# LED.net
KiCad netlist of a schematic drawn in Altium Designer
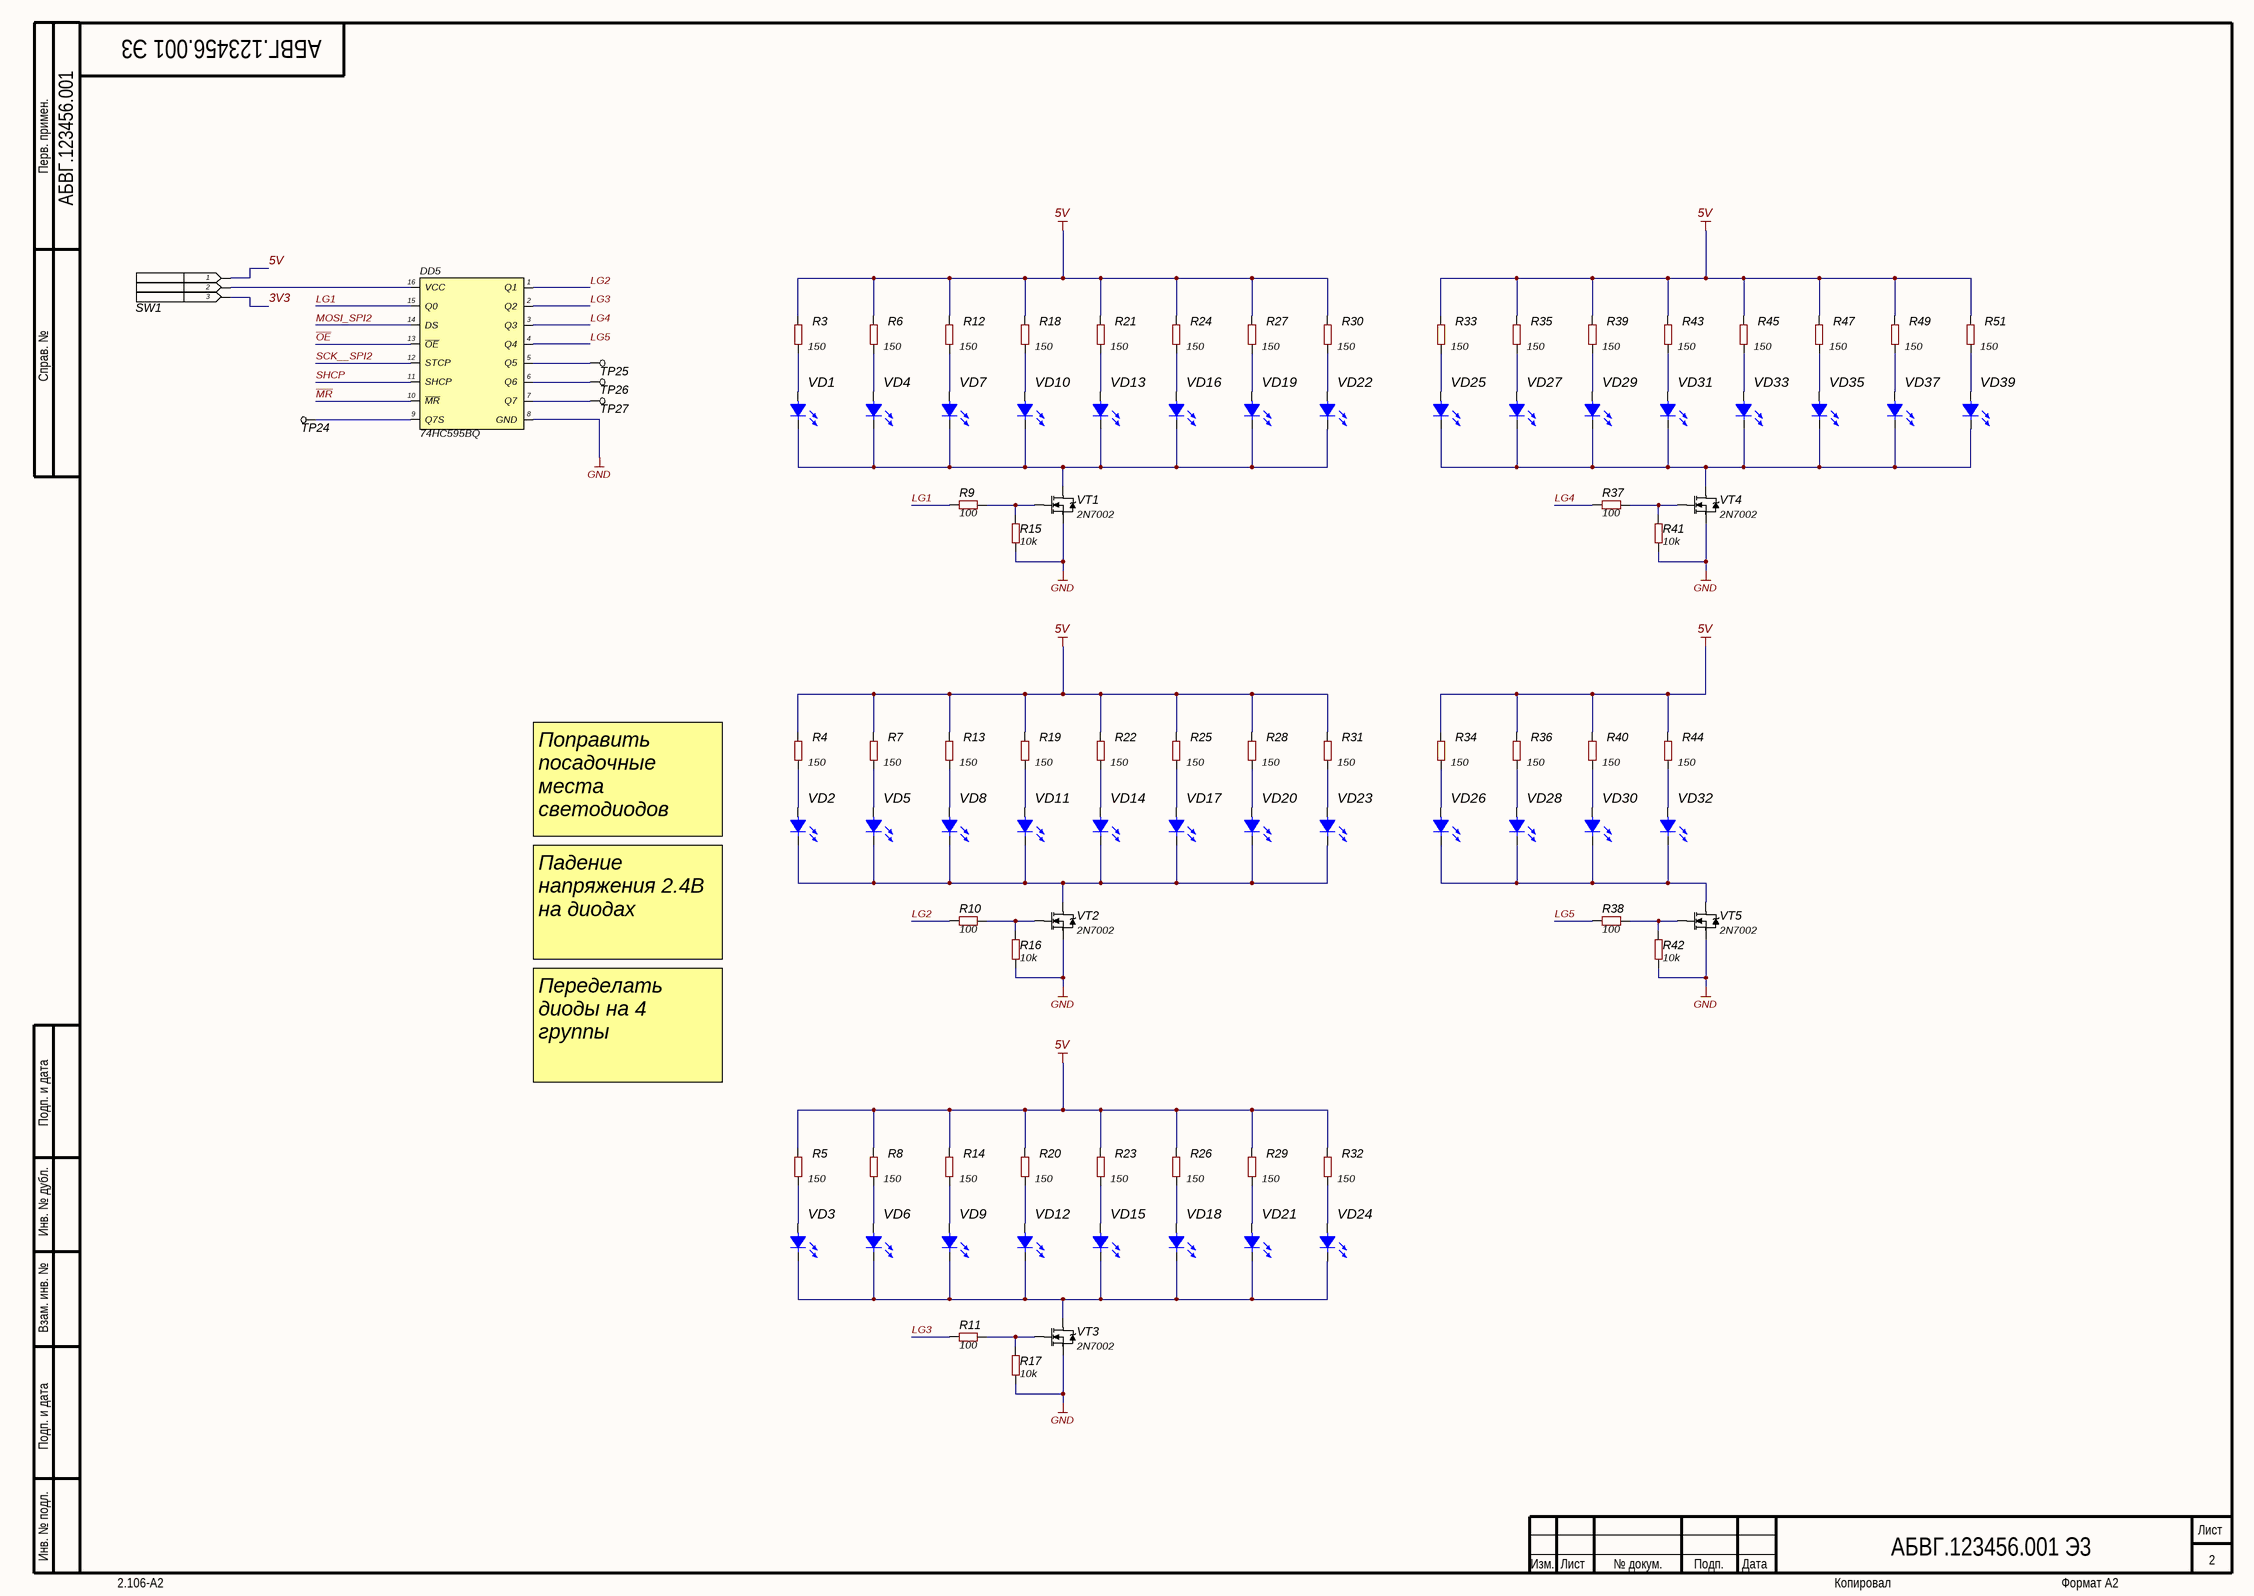
[diagram p0: LED.SchDoc]

(export (version "E")
  (design (tool "Eeschema 10.0.6"))
  (components
    (comp (ref "DD5")
      (value "74HC595BQ")
      (footprint "16-DHVQFN")
      (libsource (lib "ic-logic") (part "74HC595BQ"))
    )
    (comp (ref "R3")
      (value "150")
      (footprint "RES: 0603")
      (fields
        (field (name "MANUFACTURER") "Yageo")
        (field (name "PARTNUMBER") "RC0603JR-07100RL")
        (field (name "VALUEMANUFACTURERPARTNUMBER") "Resistor film, 150, , 0603, 0.1W, -55...+125°C")
      )
      (libsource (lib "resistor") (part "Resistor_0603"))
    )
    (comp (ref "R4")
      (value "150")
      (footprint "RES: 0603")
      (fields
        (field (name "MANUFACTURER") "Yageo")
        (field (name "PARTNUMBER") "RC0603JR-07100RL")
        (field (name "VALUEMANUFACTURERPARTNUMBER") "Resistor film, 150, , 0603, 0.1W, -55...+125°C")
      )
      (libsource (lib "resistor") (part "Resistor_0603"))
    )
    (comp (ref "R5")
      (value "150")
      (footprint "RES: 0603")
      (fields
        (field (name "MANUFACTURER") "Yageo")
        (field (name "PARTNUMBER") "RC0603JR-07100RL")
        (field (name "VALUEMANUFACTURERPARTNUMBER") "Resistor film, 150, , 0603, 0.1W, -55...+125°C")
      )
      (libsource (lib "resistor") (part "Resistor_0603"))
    )
    (comp (ref "R6")
      (value "150")
      (footprint "RES: 0603")
      (fields
        (field (name "MANUFACTURER") "Yageo")
        (field (name "PARTNUMBER") "RC0603JR-07100RL")
        (field (name "VALUEMANUFACTURERPARTNUMBER") "Resistor film, 150, , 0603, 0.1W, -55...+125°C")
      )
      (libsource (lib "resistor") (part "Resistor_0603"))
    )
    (comp (ref "R7")
      (value "150")
      (footprint "RES: 0603")
      (fields
        (field (name "MANUFACTURER") "Yageo")
        (field (name "PARTNUMBER") "RC0603JR-07100RL")
        (field (name "VALUEMANUFACTURERPARTNUMBER") "Resistor film, 150, , 0603, 0.1W, -55...+125°C")
      )
      (libsource (lib "resistor") (part "Resistor_0603"))
    )
    (comp (ref "R8")
      (value "150")
      (footprint "RES: 0603")
      (fields
        (field (name "MANUFACTURER") "Yageo")
        (field (name "PARTNUMBER") "RC0603JR-07100RL")
        (field (name "VALUEMANUFACTURERPARTNUMBER") "Resistor film, 150, , 0603, 0.1W, -55...+125°C")
      )
      (libsource (lib "resistor") (part "Resistor_0603"))
    )
    (comp (ref "R9")
      (value "100")
      (footprint "RES: 0603")
      (fields
        (field (name "MANUFACTURER") "Yageo")
        (field (name "PARTNUMBER") "RC0603JR-07100RL")
        (field (name "VALUEMANUFACTURERPARTNUMBER") "Resistor film, 100, , 0603, 0.1W, -55...+125°C")
      )
      (libsource (lib "") (part "Resistor_0603_1"))
    )
    (comp (ref "R10")
      (value "100")
      (footprint "RES: 0603")
      (fields
        (field (name "MANUFACTURER") "Yageo")
        (field (name "PARTNUMBER") "RC0603JR-07100RL")
        (field (name "VALUEMANUFACTURERPARTNUMBER") "Resistor film, 100, , 0603, 0.1W, -55...+125°C")
      )
      (libsource (lib "") (part "Resistor_0603_1"))
    )
    (comp (ref "R11")
      (value "100")
      (footprint "RES: 0603")
      (fields
        (field (name "MANUFACTURER") "Yageo")
        (field (name "PARTNUMBER") "RC0603JR-07100RL")
        (field (name "VALUEMANUFACTURERPARTNUMBER") "Resistor film, 100, , 0603, 0.1W, -55...+125°C")
      )
      (libsource (lib "") (part "Resistor_0603_1"))
    )
    (comp (ref "R12")
      (value "150")
      (footprint "RES: 0603")
      (fields
        (field (name "MANUFACTURER") "Yageo")
        (field (name "PARTNUMBER") "RC0603JR-07100RL")
        (field (name "VALUEMANUFACTURERPARTNUMBER") "Resistor film, 150, , 0603, 0.1W, -55...+125°C")
      )
      (libsource (lib "resistor") (part "Resistor_0603"))
    )
    (comp (ref "R13")
      (value "150")
      (footprint "RES: 0603")
      (fields
        (field (name "MANUFACTURER") "Yageo")
        (field (name "PARTNUMBER") "RC0603JR-07100RL")
        (field (name "VALUEMANUFACTURERPARTNUMBER") "Resistor film, 150, , 0603, 0.1W, -55...+125°C")
      )
      (libsource (lib "resistor") (part "Resistor_0603"))
    )
    (comp (ref "R14")
      (value "150")
      (footprint "RES: 0603")
      (fields
        (field (name "MANUFACTURER") "Yageo")
        (field (name "PARTNUMBER") "RC0603JR-07100RL")
        (field (name "VALUEMANUFACTURERPARTNUMBER") "Resistor film, 150, , 0603, 0.1W, -55...+125°C")
      )
      (libsource (lib "resistor") (part "Resistor_0603"))
    )
    (comp (ref "R15")
      (value "10k")
      (footprint "RES: 0603")
      (fields
        (field (name "MANUFACTURER") "Yageo")
        (field (name "PARTNUMBER") "RC0603JR-07100RL")
        (field (name "VALUEMANUFACTURERPARTNUMBER") "Resistor film, 10k, , 0603, 0.1W, -55...+125°C")
      )
      (libsource (lib "resistor") (part "Resistor_0603"))
    )
    (comp (ref "R16")
      (value "10k")
      (footprint "RES: 0603")
      (fields
        (field (name "MANUFACTURER") "Yageo")
        (field (name "PARTNUMBER") "RC0603JR-07100RL")
        (field (name "VALUEMANUFACTURERPARTNUMBER") "Resistor film, 10k, , 0603, 0.1W, -55...+125°C")
      )
      (libsource (lib "resistor") (part "Resistor_0603"))
    )
    (comp (ref "R17")
      (value "10k")
      (footprint "RES: 0603")
      (fields
        (field (name "MANUFACTURER") "Yageo")
        (field (name "PARTNUMBER") "RC0603JR-07100RL")
        (field (name "VALUEMANUFACTURERPARTNUMBER") "Resistor film, 10k, , 0603, 0.1W, -55...+125°C")
      )
      (libsource (lib "resistor") (part "Resistor_0603"))
    )
    (comp (ref "R18")
      (value "150")
      (footprint "RES: 0603")
      (fields
        (field (name "MANUFACTURER") "Yageo")
        (field (name "PARTNUMBER") "RC0603JR-07100RL")
        (field (name "VALUEMANUFACTURERPARTNUMBER") "Resistor film, 150, , 0603, 0.1W, -55...+125°C")
      )
      (libsource (lib "resistor") (part "Resistor_0603"))
    )
    (comp (ref "R19")
      (value "150")
      (footprint "RES: 0603")
      (fields
        (field (name "MANUFACTURER") "Yageo")
        (field (name "PARTNUMBER") "RC0603JR-07100RL")
        (field (name "VALUEMANUFACTURERPARTNUMBER") "Resistor film, 150, , 0603, 0.1W, -55...+125°C")
      )
      (libsource (lib "resistor") (part "Resistor_0603"))
    )
    (comp (ref "R20")
      (value "150")
      (footprint "RES: 0603")
      (fields
        (field (name "MANUFACTURER") "Yageo")
        (field (name "PARTNUMBER") "RC0603JR-07100RL")
        (field (name "VALUEMANUFACTURERPARTNUMBER") "Resistor film, 150, , 0603, 0.1W, -55...+125°C")
      )
      (libsource (lib "resistor") (part "Resistor_0603"))
    )
    (comp (ref "R21")
      (value "150")
      (footprint "RES: 0603")
      (fields
        (field (name "MANUFACTURER") "Yageo")
        (field (name "PARTNUMBER") "RC0603JR-07100RL")
        (field (name "VALUEMANUFACTURERPARTNUMBER") "Resistor film, 150, , 0603, 0.1W, -55...+125°C")
      )
      (libsource (lib "resistor") (part "Resistor_0603"))
    )
    (comp (ref "R22")
      (value "150")
      (footprint "RES: 0603")
      (fields
        (field (name "MANUFACTURER") "Yageo")
        (field (name "PARTNUMBER") "RC0603JR-07100RL")
        (field (name "VALUEMANUFACTURERPARTNUMBER") "Resistor film, 150, , 0603, 0.1W, -55...+125°C")
      )
      (libsource (lib "resistor") (part "Resistor_0603"))
    )
    (comp (ref "R23")
      (value "150")
      (footprint "RES: 0603")
      (fields
        (field (name "MANUFACTURER") "Yageo")
        (field (name "PARTNUMBER") "RC0603JR-07100RL")
        (field (name "VALUEMANUFACTURERPARTNUMBER") "Resistor film, 150, , 0603, 0.1W, -55...+125°C")
      )
      (libsource (lib "resistor") (part "Resistor_0603"))
    )
    (comp (ref "R24")
      (value "150")
      (footprint "RES: 0603")
      (fields
        (field (name "MANUFACTURER") "Yageo")
        (field (name "PARTNUMBER") "RC0603JR-07100RL")
        (field (name "VALUEMANUFACTURERPARTNUMBER") "Resistor film, 150, , 0603, 0.1W, -55...+125°C")
      )
      (libsource (lib "resistor") (part "Resistor_0603"))
    )
    (comp (ref "R25")
      (value "150")
      (footprint "RES: 0603")
      (fields
        (field (name "MANUFACTURER") "Yageo")
        (field (name "PARTNUMBER") "RC0603JR-07100RL")
        (field (name "VALUEMANUFACTURERPARTNUMBER") "Resistor film, 150, , 0603, 0.1W, -55...+125°C")
      )
      (libsource (lib "resistor") (part "Resistor_0603"))
    )
    (comp (ref "R26")
      (value "150")
      (footprint "RES: 0603")
      (fields
        (field (name "MANUFACTURER") "Yageo")
        (field (name "PARTNUMBER") "RC0603JR-07100RL")
        (field (name "VALUEMANUFACTURERPARTNUMBER") "Resistor film, 150, , 0603, 0.1W, -55...+125°C")
      )
      (libsource (lib "resistor") (part "Resistor_0603"))
    )
    (comp (ref "R27")
      (value "150")
      (footprint "RES: 0603")
      (fields
        (field (name "MANUFACTURER") "Yageo")
        (field (name "PARTNUMBER") "RC0603JR-07100RL")
        (field (name "VALUEMANUFACTURERPARTNUMBER") "Resistor film, 150, , 0603, 0.1W, -55...+125°C")
      )
      (libsource (lib "resistor") (part "Resistor_0603"))
    )
    (comp (ref "R28")
      (value "150")
      (footprint "RES: 0603")
      (fields
        (field (name "MANUFACTURER") "Yageo")
        (field (name "PARTNUMBER") "RC0603JR-07100RL")
        (field (name "VALUEMANUFACTURERPARTNUMBER") "Resistor film, 150, , 0603, 0.1W, -55...+125°C")
      )
      (libsource (lib "resistor") (part "Resistor_0603"))
    )
    (comp (ref "R29")
      (value "150")
      (footprint "RES: 0603")
      (fields
        (field (name "MANUFACTURER") "Yageo")
        (field (name "PARTNUMBER") "RC0603JR-07100RL")
        (field (name "VALUEMANUFACTURERPARTNUMBER") "Resistor film, 150, , 0603, 0.1W, -55...+125°C")
      )
      (libsource (lib "resistor") (part "Resistor_0603"))
    )
    (comp (ref "R30")
      (value "150")
      (footprint "RES: 0603")
      (fields
        (field (name "MANUFACTURER") "Yageo")
        (field (name "PARTNUMBER") "RC0603JR-07100RL")
        (field (name "VALUEMANUFACTURERPARTNUMBER") "Resistor film, 150, , 0603, 0.1W, -55...+125°C")
      )
      (libsource (lib "resistor") (part "Resistor_0603"))
    )
    (comp (ref "R31")
      (value "150")
      (footprint "RES: 0603")
      (fields
        (field (name "MANUFACTURER") "Yageo")
        (field (name "PARTNUMBER") "RC0603JR-07100RL")
        (field (name "VALUEMANUFACTURERPARTNUMBER") "Resistor film, 150, , 0603, 0.1W, -55...+125°C")
      )
      (libsource (lib "resistor") (part "Resistor_0603"))
    )
    (comp (ref "R32")
      (value "150")
      (footprint "RES: 0603")
      (fields
        (field (name "MANUFACTURER") "Yageo")
        (field (name "PARTNUMBER") "RC0603JR-07100RL")
        (field (name "VALUEMANUFACTURERPARTNUMBER") "Resistor film, 150, , 0603, 0.1W, -55...+125°C")
      )
      (libsource (lib "resistor") (part "Resistor_0603"))
    )
    (comp (ref "R33")
      (value "150")
      (footprint "RES: 0603")
      (fields
        (field (name "MANUFACTURER") "Yageo")
        (field (name "PARTNUMBER") "RC0603JR-07100RL")
        (field (name "VALUEMANUFACTURERPARTNUMBER") "Resistor film, 150, , 0603, 0.1W, -55...+125°C")
      )
      (libsource (lib "resistor") (part "Resistor_0603"))
    )
    (comp (ref "R34")
      (value "150")
      (footprint "RES: 0603")
      (fields
        (field (name "MANUFACTURER") "Yageo")
        (field (name "PARTNUMBER") "RC0603JR-07100RL")
        (field (name "VALUEMANUFACTURERPARTNUMBER") "Resistor film, 150, , 0603, 0.1W, -55...+125°C")
      )
      (libsource (lib "resistor") (part "Resistor_0603"))
    )
    (comp (ref "R35")
      (value "150")
      (footprint "RES: 0603")
      (fields
        (field (name "MANUFACTURER") "Yageo")
        (field (name "PARTNUMBER") "RC0603JR-07100RL")
        (field (name "VALUEMANUFACTURERPARTNUMBER") "Resistor film, 150, , 0603, 0.1W, -55...+125°C")
      )
      (libsource (lib "resistor") (part "Resistor_0603"))
    )
    (comp (ref "R36")
      (value "150")
      (footprint "RES: 0603")
      (fields
        (field (name "MANUFACTURER") "Yageo")
        (field (name "PARTNUMBER") "RC0603JR-07100RL")
        (field (name "VALUEMANUFACTURERPARTNUMBER") "Resistor film, 150, , 0603, 0.1W, -55...+125°C")
      )
      (libsource (lib "resistor") (part "Resistor_0603"))
    )
    (comp (ref "R37")
      (value "100")
      (footprint "RES: 0603")
      (fields
        (field (name "MANUFACTURER") "Yageo")
        (field (name "PARTNUMBER") "RC0603JR-07100RL")
        (field (name "VALUEMANUFACTURERPARTNUMBER") "Resistor film, 100, , 0603, 0.1W, -55...+125°C")
      )
      (libsource (lib "") (part "Resistor_0603_1"))
    )
    (comp (ref "R38")
      (value "100")
      (footprint "RES: 0603")
      (fields
        (field (name "MANUFACTURER") "Yageo")
        (field (name "PARTNUMBER") "RC0603JR-07100RL")
        (field (name "VALUEMANUFACTURERPARTNUMBER") "Resistor film, 100, , 0603, 0.1W, -55...+125°C")
      )
      (libsource (lib "") (part "Resistor_0603_1"))
    )
    (comp (ref "R39")
      (value "150")
      (footprint "RES: 0603")
      (fields
        (field (name "MANUFACTURER") "Yageo")
        (field (name "PARTNUMBER") "RC0603JR-07100RL")
        (field (name "VALUEMANUFACTURERPARTNUMBER") "Resistor film, 150, , 0603, 0.1W, -55...+125°C")
      )
      (libsource (lib "resistor") (part "Resistor_0603"))
    )
    (comp (ref "R40")
      (value "150")
      (footprint "RES: 0603")
      (fields
        (field (name "MANUFACTURER") "Yageo")
        (field (name "PARTNUMBER") "RC0603JR-07100RL")
        (field (name "VALUEMANUFACTURERPARTNUMBER") "Resistor film, 150, , 0603, 0.1W, -55...+125°C")
      )
      (libsource (lib "resistor") (part "Resistor_0603"))
    )
    (comp (ref "R41")
      (value "10k")
      (footprint "RES: 0603")
      (fields
        (field (name "MANUFACTURER") "Yageo")
        (field (name "PARTNUMBER") "RC0603JR-07100RL")
        (field (name "VALUEMANUFACTURERPARTNUMBER") "Resistor film, 10k, , 0603, 0.1W, -55...+125°C")
      )
      (libsource (lib "resistor") (part "Resistor_0603"))
    )
    (comp (ref "R42")
      (value "10k")
      (footprint "RES: 0603")
      (fields
        (field (name "MANUFACTURER") "Yageo")
        (field (name "PARTNUMBER") "RC0603JR-07100RL")
        (field (name "VALUEMANUFACTURERPARTNUMBER") "Resistor film, 10k, , 0603, 0.1W, -55...+125°C")
      )
      (libsource (lib "resistor") (part "Resistor_0603"))
    )
    (comp (ref "R43")
      (value "150")
      (footprint "RES: 0603")
      (fields
        (field (name "MANUFACTURER") "Yageo")
        (field (name "PARTNUMBER") "RC0603JR-07100RL")
        (field (name "VALUEMANUFACTURERPARTNUMBER") "Resistor film, 150, , 0603, 0.1W, -55...+125°C")
      )
      (libsource (lib "resistor") (part "Resistor_0603"))
    )
    (comp (ref "R44")
      (value "150")
      (footprint "RES: 0603")
      (fields
        (field (name "MANUFACTURER") "Yageo")
        (field (name "PARTNUMBER") "RC0603JR-07100RL")
        (field (name "VALUEMANUFACTURERPARTNUMBER") "Resistor film, 150, , 0603, 0.1W, -55...+125°C")
      )
      (libsource (lib "resistor") (part "Resistor_0603"))
    )
    (comp (ref "R45")
      (value "150")
      (footprint "RES: 0603")
      (fields
        (field (name "MANUFACTURER") "Yageo")
        (field (name "PARTNUMBER") "RC0603JR-07100RL")
        (field (name "VALUEMANUFACTURERPARTNUMBER") "Resistor film, 150, , 0603, 0.1W, -55...+125°C")
      )
      (libsource (lib "resistor") (part "Resistor_0603"))
    )
    (comp (ref "R47")
      (value "150")
      (footprint "RES: 0603")
      (fields
        (field (name "MANUFACTURER") "Yageo")
        (field (name "PARTNUMBER") "RC0603JR-07100RL")
        (field (name "VALUEMANUFACTURERPARTNUMBER") "Resistor film, 150, , 0603, 0.1W, -55...+125°C")
      )
      (libsource (lib "resistor") (part "Resistor_0603"))
    )
    (comp (ref "R49")
      (value "150")
      (footprint "RES: 0603")
      (fields
        (field (name "MANUFACTURER") "Yageo")
        (field (name "PARTNUMBER") "RC0603JR-07100RL")
        (field (name "VALUEMANUFACTURERPARTNUMBER") "Resistor film, 150, , 0603, 0.1W, -55...+125°C")
      )
      (libsource (lib "resistor") (part "Resistor_0603"))
    )
    (comp (ref "R51")
      (value "150")
      (footprint "RES: 0603")
      (fields
        (field (name "MANUFACTURER") "Yageo")
        (field (name "PARTNUMBER") "RC0603JR-07100RL")
        (field (name "VALUEMANUFACTURERPARTNUMBER") "Resistor film, 150, , 0603, 0.1W, -55...+125°C")
      )
      (libsource (lib "resistor") (part "Resistor_0603"))
    )
    (comp (ref "SW1")
      (value "Jumper")
      (footprint "JUM: 0603_3P")
      (description "N/C")
      (libsource (lib "electromechanics") (part "Jumper"))
    )
    (comp (ref "TP24")
      (value "Testpoint_HS1mm")
      (footprint "TestPoint(without hole)")
      (libsource (lib "connector") (part "Testpoint_HS1mm"))
    )
    (comp (ref "TP25")
      (value "Testpoint_HS1mm")
      (footprint "TestPoint(without hole)")
      (libsource (lib "connector") (part "Testpoint_HS1mm"))
    )
    (comp (ref "TP26")
      (value "Testpoint_HS1mm")
      (footprint "TestPoint(without hole)")
      (libsource (lib "connector") (part "Testpoint_HS1mm"))
    )
    (comp (ref "TP27")
      (value "Testpoint_HS1mm")
      (footprint "TestPoint(without hole)")
      (libsource (lib "connector") (part "Testpoint_HS1mm"))
    )
    (comp (ref "VD1")
      (value "~")
      (footprint "LED: 1206Y")
      (fields (field (name "VALUEMANUFACTURERPARTNUMBER") "LED, Green, *, *, *, -55...+150°C"))
      (libsource (lib "diode") (part "LED_single"))
    )
    (comp (ref "VD2")
      (value "~")
      (footprint "LED: 1206Y")
      (fields (field (name "VALUEMANUFACTURERPARTNUMBER") "LED, Green, *, *, *, -55...+150°C"))
      (libsource (lib "diode") (part "LED_single"))
    )
    (comp (ref "VD3")
      (value "~")
      (footprint "LED: 1206Y")
      (fields (field (name "VALUEMANUFACTURERPARTNUMBER") "LED, Green, *, *, *, -55...+150°C"))
      (libsource (lib "diode") (part "LED_single"))
    )
    (comp (ref "VD4")
      (value "~")
      (footprint "LED: 1206Y")
      (fields (field (name "VALUEMANUFACTURERPARTNUMBER") "LED, Green, *, *, *, -55...+150°C"))
      (libsource (lib "diode") (part "LED_single"))
    )
    (comp (ref "VD5")
      (value "~")
      (footprint "LED: 1206Y")
      (fields (field (name "VALUEMANUFACTURERPARTNUMBER") "LED, Green, *, *, *, -55...+150°C"))
      (libsource (lib "diode") (part "LED_single"))
    )
    (comp (ref "VD6")
      (value "~")
      (footprint "LED: 1206Y")
      (fields (field (name "VALUEMANUFACTURERPARTNUMBER") "LED, Green, *, *, *, -55...+150°C"))
      (libsource (lib "diode") (part "LED_single"))
    )
    (comp (ref "VD7")
      (value "~")
      (footprint "LED: 1206Y")
      (fields (field (name "VALUEMANUFACTURERPARTNUMBER") "LED, Green, *, *, *, -55...+150°C"))
      (libsource (lib "diode") (part "LED_single"))
    )
    (comp (ref "VD8")
      (value "~")
      (footprint "LED: 1206Y")
      (fields (field (name "VALUEMANUFACTURERPARTNUMBER") "LED, Green, *, *, *, -55...+150°C"))
      (libsource (lib "diode") (part "LED_single"))
    )
    (comp (ref "VD9")
      (value "~")
      (footprint "LED: 1206Y")
      (fields (field (name "VALUEMANUFACTURERPARTNUMBER") "LED, Green, *, *, *, -55...+150°C"))
      (libsource (lib "diode") (part "LED_single"))
    )
    (comp (ref "VD10")
      (value "~")
      (footprint "LED: 1206Y")
      (fields (field (name "VALUEMANUFACTURERPARTNUMBER") "LED, Green, *, *, *, -55...+150°C"))
      (libsource (lib "diode") (part "LED_single"))
    )
    (comp (ref "VD11")
      (value "~")
      (footprint "LED: 1206Y")
      (fields (field (name "VALUEMANUFACTURERPARTNUMBER") "LED, Green, *, *, *, -55...+150°C"))
      (libsource (lib "diode") (part "LED_single"))
    )
    (comp (ref "VD12")
      (value "~")
      (footprint "LED: 1206Y")
      (fields (field (name "VALUEMANUFACTURERPARTNUMBER") "LED, Green, *, *, *, -55...+150°C"))
      (libsource (lib "diode") (part "LED_single"))
    )
    (comp (ref "VD13")
      (value "~")
      (footprint "LED: 1206Y")
      (fields (field (name "VALUEMANUFACTURERPARTNUMBER") "LED, Green, *, *, *, -55...+150°C"))
      (libsource (lib "diode") (part "LED_single"))
    )
    (comp (ref "VD14")
      (value "~")
      (footprint "LED: 1206Y")
      (fields (field (name "VALUEMANUFACTURERPARTNUMBER") "LED, Green, *, *, *, -55...+150°C"))
      (libsource (lib "diode") (part "LED_single"))
    )
    (comp (ref "VD15")
      (value "~")
      (footprint "LED: 1206Y")
      (fields (field (name "VALUEMANUFACTURERPARTNUMBER") "LED, Green, *, *, *, -55...+150°C"))
      (libsource (lib "diode") (part "LED_single"))
    )
    (comp (ref "VD16")
      (value "~")
      (footprint "LED: 1206Y")
      (fields (field (name "VALUEMANUFACTURERPARTNUMBER") "LED, Green, *, *, *, -55...+150°C"))
      (libsource (lib "diode") (part "LED_single"))
    )
    (comp (ref "VD17")
      (value "~")
      (footprint "LED: 1206Y")
      (fields (field (name "VALUEMANUFACTURERPARTNUMBER") "LED, Green, *, *, *, -55...+150°C"))
      (libsource (lib "diode") (part "LED_single"))
    )
    (comp (ref "VD18")
      (value "~")
      (footprint "LED: 1206Y")
      (fields (field (name "VALUEMANUFACTURERPARTNUMBER") "LED, Green, *, *, *, -55...+150°C"))
      (libsource (lib "diode") (part "LED_single"))
    )
    (comp (ref "VD19")
      (value "~")
      (footprint "LED: 1206Y")
      (fields (field (name "VALUEMANUFACTURERPARTNUMBER") "LED, Green, *, *, *, -55...+150°C"))
      (libsource (lib "diode") (part "LED_single"))
    )
    (comp (ref "VD20")
      (value "~")
      (footprint "LED: 1206Y")
      (fields (field (name "VALUEMANUFACTURERPARTNUMBER") "LED, Green, *, *, *, -55...+150°C"))
      (libsource (lib "diode") (part "LED_single"))
    )
    (comp (ref "VD21")
      (value "~")
      (footprint "LED: 1206Y")
      (fields (field (name "VALUEMANUFACTURERPARTNUMBER") "LED, Green, *, *, *, -55...+150°C"))
      (libsource (lib "diode") (part "LED_single"))
    )
    (comp (ref "VD22")
      (value "~")
      (footprint "LED: 1206Y")
      (fields (field (name "VALUEMANUFACTURERPARTNUMBER") "LED, Green, *, *, *, -55...+150°C"))
      (libsource (lib "diode") (part "LED_single"))
    )
    (comp (ref "VD23")
      (value "~")
      (footprint "LED: 1206Y")
      (fields (field (name "VALUEMANUFACTURERPARTNUMBER") "LED, Green, *, *, *, -55...+150°C"))
      (libsource (lib "diode") (part "LED_single"))
    )
    (comp (ref "VD24")
      (value "~")
      (footprint "LED: 1206Y")
      (fields (field (name "VALUEMANUFACTURERPARTNUMBER") "LED, Green, *, *, *, -55...+150°C"))
      (libsource (lib "diode") (part "LED_single"))
    )
    (comp (ref "VD25")
      (value "~")
      (footprint "LED: 1206Y")
      (fields (field (name "VALUEMANUFACTURERPARTNUMBER") "LED, Green, *, *, *, -55...+150°C"))
      (libsource (lib "diode") (part "LED_single"))
    )
    (comp (ref "VD26")
      (value "~")
      (footprint "LED: 1206Y")
      (fields (field (name "VALUEMANUFACTURERPARTNUMBER") "LED, Green, *, *, *, -55...+150°C"))
      (libsource (lib "diode") (part "LED_single"))
    )
    (comp (ref "VD27")
      (value "~")
      (footprint "LED: 1206Y")
      (fields (field (name "VALUEMANUFACTURERPARTNUMBER") "LED, Green, *, *, *, -55...+150°C"))
      (libsource (lib "diode") (part "LED_single"))
    )
    (comp (ref "VD28")
      (value "~")
      (footprint "LED: 1206Y")
      (fields (field (name "VALUEMANUFACTURERPARTNUMBER") "LED, Green, *, *, *, -55...+150°C"))
      (libsource (lib "diode") (part "LED_single"))
    )
    (comp (ref "VD29")
      (value "~")
      (footprint "LED: 1206Y")
      (fields (field (name "VALUEMANUFACTURERPARTNUMBER") "LED, Green, *, *, *, -55...+150°C"))
      (libsource (lib "diode") (part "LED_single"))
    )
    (comp (ref "VD30")
      (value "~")
      (footprint "LED: 1206Y")
      (fields (field (name "VALUEMANUFACTURERPARTNUMBER") "LED, Green, *, *, *, -55...+150°C"))
      (libsource (lib "diode") (part "LED_single"))
    )
    (comp (ref "VD31")
      (value "~")
      (footprint "LED: 1206Y")
      (fields (field (name "VALUEMANUFACTURERPARTNUMBER") "LED, Green, *, *, *, -55...+150°C"))
      (libsource (lib "diode") (part "LED_single"))
    )
    (comp (ref "VD32")
      (value "~")
      (footprint "LED: 1206Y")
      (fields (field (name "VALUEMANUFACTURERPARTNUMBER") "LED, Green, *, *, *, -55...+150°C"))
      (libsource (lib "diode") (part "LED_single"))
    )
    (comp (ref "VD33")
      (value "~")
      (footprint "LED: 1206Y")
      (fields (field (name "VALUEMANUFACTURERPARTNUMBER") "LED, Green, *, *, *, -55...+150°C"))
      (libsource (lib "diode") (part "LED_single"))
    )
    (comp (ref "VD35")
      (value "~")
      (footprint "LED: 1206Y")
      (fields (field (name "VALUEMANUFACTURERPARTNUMBER") "LED, Green, *, *, *, -55...+150°C"))
      (libsource (lib "diode") (part "LED_single"))
    )
    (comp (ref "VD37")
      (value "~")
      (footprint "LED: 1206Y")
      (fields (field (name "VALUEMANUFACTURERPARTNUMBER") "LED, Green, *, *, *, -55...+150°C"))
      (libsource (lib "diode") (part "LED_single"))
    )
    (comp (ref "VD39")
      (value "~")
      (footprint "LED: 1206Y")
      (fields (field (name "VALUEMANUFACTURERPARTNUMBER") "LED, Green, *, *, *, -55...+150°C"))
      (libsource (lib "diode") (part "LED_single"))
    )
    (comp (ref "VT1")
      (value "~")
      (footprint "SOT23")
      (fields
        (field (name "MANUFACTURER") "Infineon Technologies")
        (field (name "VALUEMANUFACTURERPARTNUMBER") "MOSFET N-channel transistor, 80V, 7A, 9.1nC, 2.5W, 34mOhm, 756pF, 8-TDSON, -55...+150°C")
        (field (name "PARTNUMBER") "2N7002")
      )
      (libsource (lib "transistor") (part "MOSFET_N_132"))
    )
    (comp (ref "VT2")
      (value "~")
      (footprint "SOT23")
      (fields
        (field (name "MANUFACTURER") "Infineon Technologies")
        (field (name "VALUEMANUFACTURERPARTNUMBER") "MOSFET N-channel transistor, 80V, 7A, 9.1nC, 2.5W, 34mOhm, 756pF, 8-TDSON, -55...+150°C")
        (field (name "PARTNUMBER") "2N7002")
      )
      (libsource (lib "transistor") (part "MOSFET_N_132"))
    )
    (comp (ref "VT3")
      (value "~")
      (footprint "SOT23")
      (fields
        (field (name "MANUFACTURER") "Infineon Technologies")
        (field (name "VALUEMANUFACTURERPARTNUMBER") "MOSFET N-channel transistor, 80V, 7A, 9.1nC, 2.5W, 34mOhm, 756pF, 8-TDSON, -55...+150°C")
        (field (name "PARTNUMBER") "2N7002")
      )
      (libsource (lib "transistor") (part "MOSFET_N_132"))
    )
    (comp (ref "VT4")
      (value "~")
      (footprint "SOT23")
      (fields
        (field (name "MANUFACTURER") "Infineon Technologies")
        (field (name "VALUEMANUFACTURERPARTNUMBER") "MOSFET N-channel transistor, 80V, 7A, 9.1nC, 2.5W, 34mOhm, 756pF, 8-TDSON, -55...+150°C")
        (field (name "PARTNUMBER") "2N7002")
      )
      (libsource (lib "transistor") (part "MOSFET_N_132"))
    )
    (comp (ref "VT5")
      (value "~")
      (footprint "SOT23")
      (fields
        (field (name "MANUFACTURER") "Infineon Technologies")
        (field (name "VALUEMANUFACTURERPARTNUMBER") "MOSFET N-channel transistor, 80V, 7A, 9.1nC, 2.5W, 34mOhm, 756pF, 8-TDSON, -55...+150°C")
        (field (name "PARTNUMBER") "2N7002")
      )
      (libsource (lib "transistor") (part "MOSFET_N_132"))
    )
  )
  (nets
    (net (code "1") (name "/3V3") (class "Default")
      (node (ref "SW1") (pin "3") (pinfunction "3_3") (pintype "passive"))
    )
    (net (code "2") (name "/LG1") (class "Default")
      (node (ref "DD5") (pin "15") (pinfunction "Q0_15") (pintype "passive"))
      (node (ref "R9") (pin "1") (pinfunction "1_1") (pintype "passive"))
    )
    (net (code "3") (name "/LG2") (class "Default")
      (node (ref "DD5") (pin "1") (pinfunction "Q1_1") (pintype "passive"))
      (node (ref "R10") (pin "1") (pinfunction "1_1") (pintype "passive"))
    )
    (net (code "4") (name "/LG3") (class "Default")
      (node (ref "DD5") (pin "2") (pinfunction "Q2_2") (pintype "passive"))
      (node (ref "R11") (pin "1") (pinfunction "1_1") (pintype "passive"))
    )
    (net (code "5") (name "/LG4") (class "Default")
      (node (ref "DD5") (pin "3") (pinfunction "Q3_3") (pintype "passive"))
      (node (ref "R37") (pin "1") (pinfunction "1_1") (pintype "passive"))
    )
    (net (code "6") (name "/LG5") (class "Default")
      (node (ref "DD5") (pin "4") (pinfunction "Q4_4") (pintype "passive"))
      (node (ref "R38") (pin "1") (pinfunction "1_1") (pintype "passive"))
    )
    (net (code "7") (name "/MOSI_SPI2") (class "Default")
      (node (ref "DD5") (pin "14") (pinfunction "DS_14") (pintype "passive"))
    )
    (net (code "8") (name "/SCK__SPI2") (class "Default")
      (node (ref "DD5") (pin "12") (pinfunction "STCP_12") (pintype "passive"))
    )
    (net (code "9") (name "/SHCP") (class "Default")
      (node (ref "DD5") (pin "11") (pinfunction "SHCP_11") (pintype "passive"))
    )
    (net (code "10") (name "/~{MR}") (class "Default")
      (node (ref "DD5") (pin "10") (pinfunction "~{MR}_10") (pintype "passive"))
    )
    (net (code "11") (name "/~{OE}") (class "Default")
      (node (ref "DD5") (pin "13") (pinfunction "~{OE}_13") (pintype "passive"))
    )
    (net (code "12") (name "5V") (class "Default")
      (node (ref "R12") (pin "2") (pinfunction "2_2") (pintype "passive"))
      (node (ref "R13") (pin "2") (pinfunction "2_2") (pintype "passive"))
      (node (ref "R14") (pin "2") (pinfunction "2_2") (pintype "passive"))
      (node (ref "R18") (pin "2") (pinfunction "2_2") (pintype "passive"))
      (node (ref "R19") (pin "2") (pinfunction "2_2") (pintype "passive"))
      (node (ref "R20") (pin "2") (pinfunction "2_2") (pintype "passive"))
      (node (ref "R21") (pin "2") (pinfunction "2_2") (pintype "passive"))
      (node (ref "R22") (pin "2") (pinfunction "2_2") (pintype "passive"))
      (node (ref "R23") (pin "2") (pinfunction "2_2") (pintype "passive"))
      (node (ref "R24") (pin "2") (pinfunction "2_2") (pintype "passive"))
      (node (ref "R25") (pin "2") (pinfunction "2_2") (pintype "passive"))
      (node (ref "R26") (pin "2") (pinfunction "2_2") (pintype "passive"))
      (node (ref "R27") (pin "2") (pinfunction "2_2") (pintype "passive"))
      (node (ref "R28") (pin "2") (pinfunction "2_2") (pintype "passive"))
      (node (ref "R29") (pin "2") (pinfunction "2_2") (pintype "passive"))
      (node (ref "R3") (pin "2") (pinfunction "2_2") (pintype "passive"))
      (node (ref "R30") (pin "2") (pinfunction "2_2") (pintype "passive"))
      (node (ref "R31") (pin "2") (pinfunction "2_2") (pintype "passive"))
      (node (ref "R32") (pin "2") (pinfunction "2_2") (pintype "passive"))
      (node (ref "R33") (pin "2") (pinfunction "2_2") (pintype "passive"))
      (node (ref "R34") (pin "2") (pinfunction "2_2") (pintype "passive"))
      (node (ref "R35") (pin "2") (pinfunction "2_2") (pintype "passive"))
      (node (ref "R36") (pin "2") (pinfunction "2_2") (pintype "passive"))
      (node (ref "R39") (pin "2") (pinfunction "2_2") (pintype "passive"))
      (node (ref "R4") (pin "2") (pinfunction "2_2") (pintype "passive"))
      (node (ref "R40") (pin "2") (pinfunction "2_2") (pintype "passive"))
      (node (ref "R43") (pin "2") (pinfunction "2_2") (pintype "passive"))
      (node (ref "R44") (pin "2") (pinfunction "2_2") (pintype "passive"))
      (node (ref "R45") (pin "2") (pinfunction "2_2") (pintype "passive"))
      (node (ref "R47") (pin "2") (pinfunction "2_2") (pintype "passive"))
      (node (ref "R49") (pin "2") (pinfunction "2_2") (pintype "passive"))
      (node (ref "R5") (pin "2") (pinfunction "2_2") (pintype "passive"))
      (node (ref "R51") (pin "2") (pinfunction "2_2") (pintype "passive"))
      (node (ref "R6") (pin "2") (pinfunction "2_2") (pintype "passive"))
      (node (ref "R7") (pin "2") (pinfunction "2_2") (pintype "passive"))
      (node (ref "R8") (pin "2") (pinfunction "2_2") (pintype "passive"))
      (node (ref "SW1") (pin "1") (pinfunction "1_1") (pintype "passive"))
    )
    (net (code "13") (name "GND") (class "Default")
      (node (ref "DD5") (pin "8") (pinfunction "GND_8") (pintype "passive"))
      (node (ref "R15") (pin "1") (pinfunction "1_1") (pintype "passive"))
      (node (ref "R16") (pin "1") (pinfunction "1_1") (pintype "passive"))
      (node (ref "R17") (pin "1") (pinfunction "1_1") (pintype "passive"))
      (node (ref "R41") (pin "1") (pinfunction "1_1") (pintype "passive"))
      (node (ref "R42") (pin "1") (pinfunction "1_1") (pintype "passive"))
      (node (ref "VT1") (pin "2") (pinfunction "S_2") (pintype "passive"))
      (node (ref "VT2") (pin "2") (pinfunction "S_2") (pintype "passive"))
      (node (ref "VT3") (pin "2") (pinfunction "S_2") (pintype "passive"))
      (node (ref "VT4") (pin "2") (pinfunction "S_2") (pintype "passive"))
      (node (ref "VT5") (pin "2") (pinfunction "S_2") (pintype "passive"))
    )
    (net (code "14") (name "Net-(DD5-Q5)") (class "Default")
      (node (ref "DD5") (pin "5") (pinfunction "Q5_5") (pintype "passive"))
      (node (ref "TP25") (pin "1") (pinfunction "1_1") (pintype "passive"))
    )
    (net (code "15") (name "Net-(DD5-Q6)") (class "Default")
      (node (ref "DD5") (pin "6") (pinfunction "Q6_6") (pintype "passive"))
      (node (ref "TP26") (pin "1") (pinfunction "1_1") (pintype "passive"))
    )
    (net (code "16") (name "Net-(DD5-Q7)") (class "Default")
      (node (ref "DD5") (pin "7") (pinfunction "Q7_7") (pintype "passive"))
      (node (ref "TP27") (pin "1") (pinfunction "1_1") (pintype "passive"))
    )
    (net (code "17") (name "Net-(DD5-Q7S)") (class "Default")
      (node (ref "DD5") (pin "9") (pinfunction "Q7S_9") (pintype "passive"))
      (node (ref "TP24") (pin "1") (pinfunction "1_1") (pintype "passive"))
    )
    (net (code "18") (name "Net-(DD5-VCC)") (class "Default")
      (node (ref "DD5") (pin "16") (pinfunction "VCC_16") (pintype "passive"))
      (node (ref "SW1") (pin "2") (pinfunction "2_2") (pintype "passive"))
    )
    (net (code "19") (name "Net-(VD1-A)") (class "Default")
      (node (ref "R3") (pin "1") (pinfunction "1_1") (pintype "passive"))
      (node (ref "VD1") (pin "1") (pinfunction "A_1") (pintype "passive"))
    )
    (net (code "20") (name "Net-(VD1-C)") (class "Default")
      (node (ref "VD1") (pin "2") (pinfunction "C_2") (pintype "passive"))
      (node (ref "VD10") (pin "2") (pinfunction "C_2") (pintype "passive"))
      (node (ref "VD13") (pin "2") (pinfunction "C_2") (pintype "passive"))
      (node (ref "VD16") (pin "2") (pinfunction "C_2") (pintype "passive"))
      (node (ref "VD19") (pin "2") (pinfunction "C_2") (pintype "passive"))
      (node (ref "VD22") (pin "2") (pinfunction "C_2") (pintype "passive"))
      (node (ref "VD4") (pin "2") (pinfunction "C_2") (pintype "passive"))
      (node (ref "VD7") (pin "2") (pinfunction "C_2") (pintype "passive"))
      (node (ref "VT1") (pin "3") (pinfunction "D_3") (pintype "passive"))
    )
    (net (code "21") (name "Net-(VD2-A)") (class "Default")
      (node (ref "R4") (pin "1") (pinfunction "1_1") (pintype "passive"))
      (node (ref "VD2") (pin "1") (pinfunction "A_1") (pintype "passive"))
    )
    (net (code "22") (name "Net-(VD3-A)") (class "Default")
      (node (ref "R5") (pin "1") (pinfunction "1_1") (pintype "passive"))
      (node (ref "VD3") (pin "1") (pinfunction "A_1") (pintype "passive"))
    )
    (net (code "23") (name "Net-(VD4-A)") (class "Default")
      (node (ref "R6") (pin "1") (pinfunction "1_1") (pintype "passive"))
      (node (ref "VD4") (pin "1") (pinfunction "A_1") (pintype "passive"))
    )
    (net (code "24") (name "Net-(VD5-A)") (class "Default")
      (node (ref "R7") (pin "1") (pinfunction "1_1") (pintype "passive"))
      (node (ref "VD5") (pin "1") (pinfunction "A_1") (pintype "passive"))
    )
    (net (code "25") (name "Net-(VD6-A)") (class "Default")
      (node (ref "R8") (pin "1") (pinfunction "1_1") (pintype "passive"))
      (node (ref "VD6") (pin "1") (pinfunction "A_1") (pintype "passive"))
    )
    (net (code "26") (name "Net-(VD7-A)") (class "Default")
      (node (ref "R12") (pin "1") (pinfunction "1_1") (pintype "passive"))
      (node (ref "VD7") (pin "1") (pinfunction "A_1") (pintype "passive"))
    )
    (net (code "27") (name "Net-(VD8-A)") (class "Default")
      (node (ref "R13") (pin "1") (pinfunction "1_1") (pintype "passive"))
      (node (ref "VD8") (pin "1") (pinfunction "A_1") (pintype "passive"))
    )
    (net (code "28") (name "Net-(VD9-A)") (class "Default")
      (node (ref "R14") (pin "1") (pinfunction "1_1") (pintype "passive"))
      (node (ref "VD9") (pin "1") (pinfunction "A_1") (pintype "passive"))
    )
    (net (code "29") (name "Net-(VD10-A)") (class "Default")
      (node (ref "R18") (pin "1") (pinfunction "1_1") (pintype "passive"))
      (node (ref "VD10") (pin "1") (pinfunction "A_1") (pintype "passive"))
    )
    (net (code "30") (name "Net-(VD11-A)") (class "Default")
      (node (ref "R19") (pin "1") (pinfunction "1_1") (pintype "passive"))
      (node (ref "VD11") (pin "1") (pinfunction "A_1") (pintype "passive"))
    )
    (net (code "31") (name "Net-(VD11-C)") (class "Default")
      (node (ref "VD11") (pin "2") (pinfunction "C_2") (pintype "passive"))
      (node (ref "VD14") (pin "2") (pinfunction "C_2") (pintype "passive"))
      (node (ref "VD17") (pin "2") (pinfunction "C_2") (pintype "passive"))
      (node (ref "VD2") (pin "2") (pinfunction "C_2") (pintype "passive"))
      (node (ref "VD20") (pin "2") (pinfunction "C_2") (pintype "passive"))
      (node (ref "VD23") (pin "2") (pinfunction "C_2") (pintype "passive"))
      (node (ref "VD5") (pin "2") (pinfunction "C_2") (pintype "passive"))
      (node (ref "VD8") (pin "2") (pinfunction "C_2") (pintype "passive"))
      (node (ref "VT2") (pin "3") (pinfunction "D_3") (pintype "passive"))
    )
    (net (code "32") (name "Net-(VD12-A)") (class "Default")
      (node (ref "R20") (pin "1") (pinfunction "1_1") (pintype "passive"))
      (node (ref "VD12") (pin "1") (pinfunction "A_1") (pintype "passive"))
    )
    (net (code "33") (name "Net-(VD12-C)") (class "Default")
      (node (ref "VD12") (pin "2") (pinfunction "C_2") (pintype "passive"))
      (node (ref "VD15") (pin "2") (pinfunction "C_2") (pintype "passive"))
      (node (ref "VD18") (pin "2") (pinfunction "C_2") (pintype "passive"))
      (node (ref "VD21") (pin "2") (pinfunction "C_2") (pintype "passive"))
      (node (ref "VD24") (pin "2") (pinfunction "C_2") (pintype "passive"))
      (node (ref "VD3") (pin "2") (pinfunction "C_2") (pintype "passive"))
      (node (ref "VD6") (pin "2") (pinfunction "C_2") (pintype "passive"))
      (node (ref "VD9") (pin "2") (pinfunction "C_2") (pintype "passive"))
      (node (ref "VT3") (pin "3") (pinfunction "D_3") (pintype "passive"))
    )
    (net (code "34") (name "Net-(VD13-A)") (class "Default")
      (node (ref "R21") (pin "1") (pinfunction "1_1") (pintype "passive"))
      (node (ref "VD13") (pin "1") (pinfunction "A_1") (pintype "passive"))
    )
    (net (code "35") (name "Net-(VD14-A)") (class "Default")
      (node (ref "R22") (pin "1") (pinfunction "1_1") (pintype "passive"))
      (node (ref "VD14") (pin "1") (pinfunction "A_1") (pintype "passive"))
    )
    (net (code "36") (name "Net-(VD15-A)") (class "Default")
      (node (ref "R23") (pin "1") (pinfunction "1_1") (pintype "passive"))
      (node (ref "VD15") (pin "1") (pinfunction "A_1") (pintype "passive"))
    )
    (net (code "37") (name "Net-(VD16-A)") (class "Default")
      (node (ref "R24") (pin "1") (pinfunction "1_1") (pintype "passive"))
      (node (ref "VD16") (pin "1") (pinfunction "A_1") (pintype "passive"))
    )
    (net (code "38") (name "Net-(VD17-A)") (class "Default")
      (node (ref "R25") (pin "1") (pinfunction "1_1") (pintype "passive"))
      (node (ref "VD17") (pin "1") (pinfunction "A_1") (pintype "passive"))
    )
    (net (code "39") (name "Net-(VD18-A)") (class "Default")
      (node (ref "R26") (pin "1") (pinfunction "1_1") (pintype "passive"))
      (node (ref "VD18") (pin "1") (pinfunction "A_1") (pintype "passive"))
    )
    (net (code "40") (name "Net-(VD19-A)") (class "Default")
      (node (ref "R27") (pin "1") (pinfunction "1_1") (pintype "passive"))
      (node (ref "VD19") (pin "1") (pinfunction "A_1") (pintype "passive"))
    )
    (net (code "41") (name "Net-(VD20-A)") (class "Default")
      (node (ref "R28") (pin "1") (pinfunction "1_1") (pintype "passive"))
      (node (ref "VD20") (pin "1") (pinfunction "A_1") (pintype "passive"))
    )
    (net (code "42") (name "Net-(VD21-A)") (class "Default")
      (node (ref "R29") (pin "1") (pinfunction "1_1") (pintype "passive"))
      (node (ref "VD21") (pin "1") (pinfunction "A_1") (pintype "passive"))
    )
    (net (code "43") (name "Net-(VD22-A)") (class "Default")
      (node (ref "R30") (pin "1") (pinfunction "1_1") (pintype "passive"))
      (node (ref "VD22") (pin "1") (pinfunction "A_1") (pintype "passive"))
    )
    (net (code "44") (name "Net-(VD23-A)") (class "Default")
      (node (ref "R31") (pin "1") (pinfunction "1_1") (pintype "passive"))
      (node (ref "VD23") (pin "1") (pinfunction "A_1") (pintype "passive"))
    )
    (net (code "45") (name "Net-(VD24-A)") (class "Default")
      (node (ref "R32") (pin "1") (pinfunction "1_1") (pintype "passive"))
      (node (ref "VD24") (pin "1") (pinfunction "A_1") (pintype "passive"))
    )
    (net (code "46") (name "Net-(VD25-A)") (class "Default")
      (node (ref "R33") (pin "1") (pinfunction "1_1") (pintype "passive"))
      (node (ref "VD25") (pin "1") (pinfunction "A_1") (pintype "passive"))
    )
    (net (code "47") (name "Net-(VD25-C)") (class "Default")
      (node (ref "VD25") (pin "2") (pinfunction "C_2") (pintype "passive"))
      (node (ref "VD27") (pin "2") (pinfunction "C_2") (pintype "passive"))
      (node (ref "VD29") (pin "2") (pinfunction "C_2") (pintype "passive"))
      (node (ref "VD31") (pin "2") (pinfunction "C_2") (pintype "passive"))
      (node (ref "VD33") (pin "2") (pinfunction "C_2") (pintype "passive"))
      (node (ref "VD35") (pin "2") (pinfunction "C_2") (pintype "passive"))
      (node (ref "VD37") (pin "2") (pinfunction "C_2") (pintype "passive"))
      (node (ref "VD39") (pin "2") (pinfunction "C_2") (pintype "passive"))
      (node (ref "VT4") (pin "3") (pinfunction "D_3") (pintype "passive"))
    )
    (net (code "48") (name "Net-(VD26-A)") (class "Default")
      (node (ref "R34") (pin "1") (pinfunction "1_1") (pintype "passive"))
      (node (ref "VD26") (pin "1") (pinfunction "A_1") (pintype "passive"))
    )
    (net (code "49") (name "Net-(VD26-C)") (class "Default")
      (node (ref "VD26") (pin "2") (pinfunction "C_2") (pintype "passive"))
      (node (ref "VD28") (pin "2") (pinfunction "C_2") (pintype "passive"))
      (node (ref "VD30") (pin "2") (pinfunction "C_2") (pintype "passive"))
      (node (ref "VD32") (pin "2") (pinfunction "C_2") (pintype "passive"))
      (node (ref "VT5") (pin "3") (pinfunction "D_3") (pintype "passive"))
    )
    (net (code "50") (name "Net-(VD27-A)") (class "Default")
      (node (ref "R35") (pin "1") (pinfunction "1_1") (pintype "passive"))
      (node (ref "VD27") (pin "1") (pinfunction "A_1") (pintype "passive"))
    )
    (net (code "51") (name "Net-(VD28-A)") (class "Default")
      (node (ref "R36") (pin "1") (pinfunction "1_1") (pintype "passive"))
      (node (ref "VD28") (pin "1") (pinfunction "A_1") (pintype "passive"))
    )
    (net (code "52") (name "Net-(VD29-A)") (class "Default")
      (node (ref "R39") (pin "1") (pinfunction "1_1") (pintype "passive"))
      (node (ref "VD29") (pin "1") (pinfunction "A_1") (pintype "passive"))
    )
    (net (code "53") (name "Net-(VD30-A)") (class "Default")
      (node (ref "R40") (pin "1") (pinfunction "1_1") (pintype "passive"))
      (node (ref "VD30") (pin "1") (pinfunction "A_1") (pintype "passive"))
    )
    (net (code "54") (name "Net-(VD31-A)") (class "Default")
      (node (ref "R43") (pin "1") (pinfunction "1_1") (pintype "passive"))
      (node (ref "VD31") (pin "1") (pinfunction "A_1") (pintype "passive"))
    )
    (net (code "55") (name "Net-(VD32-A)") (class "Default")
      (node (ref "R44") (pin "1") (pinfunction "1_1") (pintype "passive"))
      (node (ref "VD32") (pin "1") (pinfunction "A_1") (pintype "passive"))
    )
    (net (code "56") (name "Net-(VD33-A)") (class "Default")
      (node (ref "R45") (pin "1") (pinfunction "1_1") (pintype "passive"))
      (node (ref "VD33") (pin "1") (pinfunction "A_1") (pintype "passive"))
    )
    (net (code "57") (name "Net-(VD35-A)") (class "Default")
      (node (ref "R47") (pin "1") (pinfunction "1_1") (pintype "passive"))
      (node (ref "VD35") (pin "1") (pinfunction "A_1") (pintype "passive"))
    )
    (net (code "58") (name "Net-(VD37-A)") (class "Default")
      (node (ref "R49") (pin "1") (pinfunction "1_1") (pintype "passive"))
      (node (ref "VD37") (pin "1") (pinfunction "A_1") (pintype "passive"))
    )
    (net (code "59") (name "Net-(VD39-A)") (class "Default")
      (node (ref "R51") (pin "1") (pinfunction "1_1") (pintype "passive"))
      (node (ref "VD39") (pin "1") (pinfunction "A_1") (pintype "passive"))
    )
    (net (code "60") (name "Net-(VT1-G)") (class "Default")
      (node (ref "R15") (pin "2") (pinfunction "2_2") (pintype "passive"))
      (node (ref "R9") (pin "2") (pinfunction "2_2") (pintype "passive"))
      (node (ref "VT1") (pin "1") (pinfunction "G_1") (pintype "passive"))
    )
    (net (code "61") (name "Net-(VT2-G)") (class "Default")
      (node (ref "R10") (pin "2") (pinfunction "2_2") (pintype "passive"))
      (node (ref "R16") (pin "2") (pinfunction "2_2") (pintype "passive"))
      (node (ref "VT2") (pin "1") (pinfunction "G_1") (pintype "passive"))
    )
    (net (code "62") (name "Net-(VT3-G)") (class "Default")
      (node (ref "R11") (pin "2") (pinfunction "2_2") (pintype "passive"))
      (node (ref "R17") (pin "2") (pinfunction "2_2") (pintype "passive"))
      (node (ref "VT3") (pin "1") (pinfunction "G_1") (pintype "passive"))
    )
    (net (code "63") (name "Net-(VT4-G)") (class "Default")
      (node (ref "R37") (pin "2") (pinfunction "2_2") (pintype "passive"))
      (node (ref "R41") (pin "2") (pinfunction "2_2") (pintype "passive"))
      (node (ref "VT4") (pin "1") (pinfunction "G_1") (pintype "passive"))
    )
    (net (code "64") (name "Net-(VT5-G)") (class "Default")
      (node (ref "R38") (pin "2") (pinfunction "2_2") (pintype "passive"))
      (node (ref "R42") (pin "2") (pinfunction "2_2") (pintype "passive"))
      (node (ref "VT5") (pin "1") (pinfunction "G_1") (pintype "passive"))
    )
  )
)
